# A4973.net
KiCad netlist of a schematic drawn in EAGLE
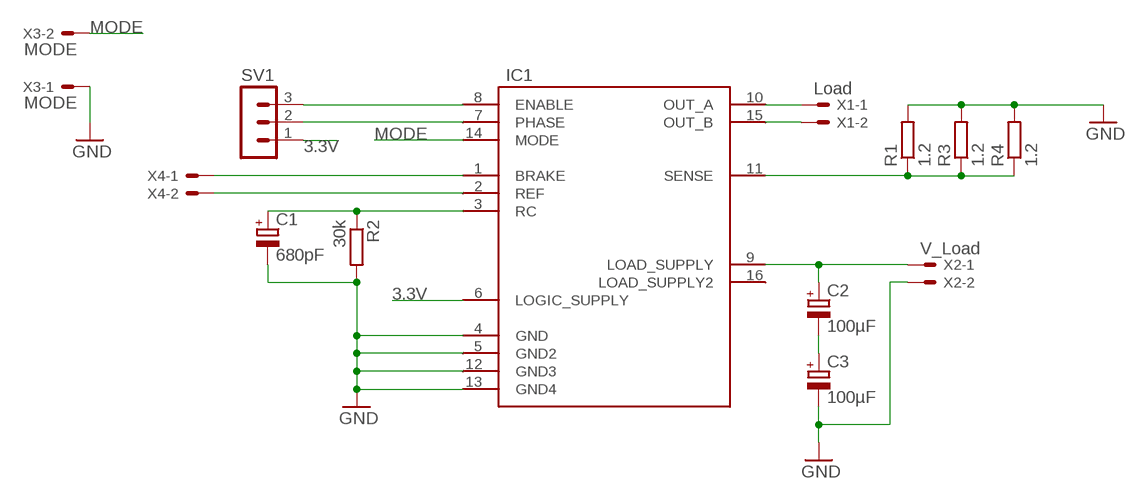
[diagram p0: schematic, sheet 1]

(export (version "E")
  (design (tool "Eeschema 10.0.6"))
  (components
    (comp (ref "C1")
      (value "680pF")
      (footprint "eagle-import:ETR4")
      (libsource (lib "eagle-import") (part "CPOL-EUETR4"))
    )
    (comp (ref "C2")
      (value "100µF")
      (footprint "eagle-import:E5-13")
      (libsource (lib "eagle-import") (part "CPOL-EUE5-13"))
    )
    (comp (ref "C3")
      (value "100µF")
      (footprint "eagle-import:E5-13")
      (libsource (lib "eagle-import") (part "CPOL-EUE5-13"))
    )
    (comp (ref "IC1")
      (value "A4973DIL")
      (footprint "eagle-import:DIL16")
      (libsource (lib "eagle-import") (part "A4973DIL"))
    )
    (comp (ref "R1")
      (value "1.2")
      (footprint "eagle-import:0207_10")
      (libsource (lib "eagle-import") (part "resistor_R-EU_0207/10"))
    )
    (comp (ref "R2")
      (value "30k")
      (footprint "eagle-import:0207_12")
      (libsource (lib "eagle-import") (part "R-EU_0207/12"))
    )
    (comp (ref "R3")
      (value "1.2")
      (footprint "eagle-import:0207_10")
      (libsource (lib "eagle-import") (part "resistor_R-EU_0207/10"))
    )
    (comp (ref "R4")
      (value "1.2")
      (footprint "eagle-import:0207_10")
      (libsource (lib "eagle-import") (part "resistor_R-EU_0207/10"))
    )
    (comp (ref "SV1")
      (value "MA03-1")
      (footprint "eagle-import:MA03-1")
      (libsource (lib "eagle-import") (part "MA03-1"))
    )
    (comp (ref "X1")
      (value "Load")
      (footprint "eagle-import:22-23-2021")
      (fields (field (name "MF") "MOLEX") (field (name "MPN") "22-23-2021"))
      (libsource (lib "eagle-import") (part "22-23-2021"))
    )
    (comp (ref "X2")
      (value "V_Load")
      (footprint "eagle-import:22-23-2021")
      (fields (field (name "MF") "MOLEX") (field (name "MPN") "22-23-2021"))
      (libsource (lib "eagle-import") (part "22-23-2021"))
    )
    (comp (ref "X3")
      (value "MODE")
      (footprint "eagle-import:332-02")
      (libsource (lib "eagle-import") (part "332-02"))
    )
    (comp (ref "X4")
      (value "332-02")
      (footprint "eagle-import:332-02")
      (libsource (lib "eagle-import") (part "332-02"))
    )
  )
  (nets
    (net (code "1") (name "/3.3V") (class "Default")
      (node (ref "IC1") (pin "6") (pinfunction "LOGIC_SUPPLY_6") (pintype "bidirectional"))
      (node (ref "SV1") (pin "1") (pinfunction "1_1") (pintype "passive"))
    )
    (net (code "2") (name "/MODE") (class "Default")
      (node (ref "IC1") (pin "14") (pinfunction "MODE_14") (pintype "bidirectional"))
      (node (ref "X3") (pin "2") (pinfunction "S_2") (pintype "passive"))
    )
    (net (code "3") (name "GND") (class "Default")
      (node (ref "C1") (pin "-") (pinfunction "-_-") (pintype "passive"))
      (node (ref "C3") (pin "-") (pinfunction "-_-") (pintype "passive"))
      (node (ref "IC1") (pin "12") (pinfunction "GND3_12") (pintype "bidirectional"))
      (node (ref "IC1") (pin "13") (pinfunction "GND4_13") (pintype "bidirectional"))
      (node (ref "IC1") (pin "4") (pinfunction "GND_4") (pintype "bidirectional"))
      (node (ref "IC1") (pin "5") (pinfunction "GND2_5") (pintype "bidirectional"))
      (node (ref "R1") (pin "2") (pinfunction "2_2") (pintype "passive"))
      (node (ref "R2") (pin "2") (pinfunction "2_2") (pintype "passive"))
      (node (ref "R3") (pin "2") (pinfunction "2_2") (pintype "passive"))
      (node (ref "R4") (pin "2") (pinfunction "2_2") (pintype "passive"))
      (node (ref "X2") (pin "2") (pinfunction "S_2") (pintype "passive"))
      (node (ref "X3") (pin "1") (pinfunction "S_1") (pintype "passive"))
    )
    (net (code "4") (name "Net-(C2-Pad-)") (class "Default")
      (node (ref "C2") (pin "-") (pinfunction "-_-") (pintype "passive"))
      (node (ref "C3") (pin "+") (pinfunction "+_+") (pintype "passive"))
    )
    (net (code "5") (name "Net-(IC1-BRAKE)") (class "Default")
      (node (ref "IC1") (pin "1") (pinfunction "BRAKE_1") (pintype "bidirectional"))
      (node (ref "X4") (pin "1") (pinfunction "S_1") (pintype "passive"))
    )
    (net (code "6") (name "Net-(IC1-ENABLE)") (class "Default")
      (node (ref "IC1") (pin "8") (pinfunction "ENABLE_8") (pintype "bidirectional"))
      (node (ref "SV1") (pin "3") (pinfunction "3_3") (pintype "passive"))
    )
    (net (code "7") (name "Net-(IC1-LOAD_SUPPLY)") (class "Default")
      (node (ref "C2") (pin "+") (pinfunction "+_+") (pintype "passive"))
      (node (ref "IC1") (pin "9") (pinfunction "LOAD_SUPPLY_9") (pintype "bidirectional"))
      (node (ref "X2") (pin "1") (pinfunction "S_1") (pintype "passive"))
    )
    (net (code "8") (name "Net-(IC1-OUT_A)") (class "Default")
      (node (ref "IC1") (pin "10") (pinfunction "OUT_A_10") (pintype "bidirectional"))
      (node (ref "X1") (pin "1") (pinfunction "S_1") (pintype "passive"))
    )
    (net (code "9") (name "Net-(IC1-OUT_B)") (class "Default")
      (node (ref "IC1") (pin "15") (pinfunction "OUT_B_15") (pintype "bidirectional"))
      (node (ref "X1") (pin "2") (pinfunction "S_2") (pintype "passive"))
    )
    (net (code "10") (name "Net-(IC1-PHASE)") (class "Default")
      (node (ref "IC1") (pin "7") (pinfunction "PHASE_7") (pintype "bidirectional"))
      (node (ref "SV1") (pin "2") (pinfunction "2_2") (pintype "passive"))
    )
    (net (code "11") (name "Net-(IC1-RC)") (class "Default")
      (node (ref "C1") (pin "+") (pinfunction "+_+") (pintype "passive"))
      (node (ref "IC1") (pin "3") (pinfunction "RC_3") (pintype "bidirectional"))
      (node (ref "R2") (pin "1") (pinfunction "1_1") (pintype "passive"))
    )
    (net (code "12") (name "Net-(IC1-REF)") (class "Default")
      (node (ref "IC1") (pin "2") (pinfunction "REF_2") (pintype "bidirectional"))
      (node (ref "X4") (pin "2") (pinfunction "S_2") (pintype "passive"))
    )
    (net (code "13") (name "Net-(IC1-SENSE)") (class "Default")
      (node (ref "IC1") (pin "11") (pinfunction "SENSE_11") (pintype "bidirectional"))
      (node (ref "R1") (pin "1") (pinfunction "1_1") (pintype "passive"))
      (node (ref "R3") (pin "1") (pinfunction "1_1") (pintype "passive"))
      (node (ref "R4") (pin "1") (pinfunction "1_1") (pintype "passive"))
    )
    (net (code "14") (name "unconnected-(IC1-LOAD_SUPPLY2-Pad16)") (class "Default")
      (node (ref "IC1") (pin "16") (pinfunction "LOAD_SUPPLY2_16") (pintype "bidirectional"))
    )
  )
)
